# Power_Distribution_Board_B.net
KiCad netlist of a schematic drawn in Altium Designer
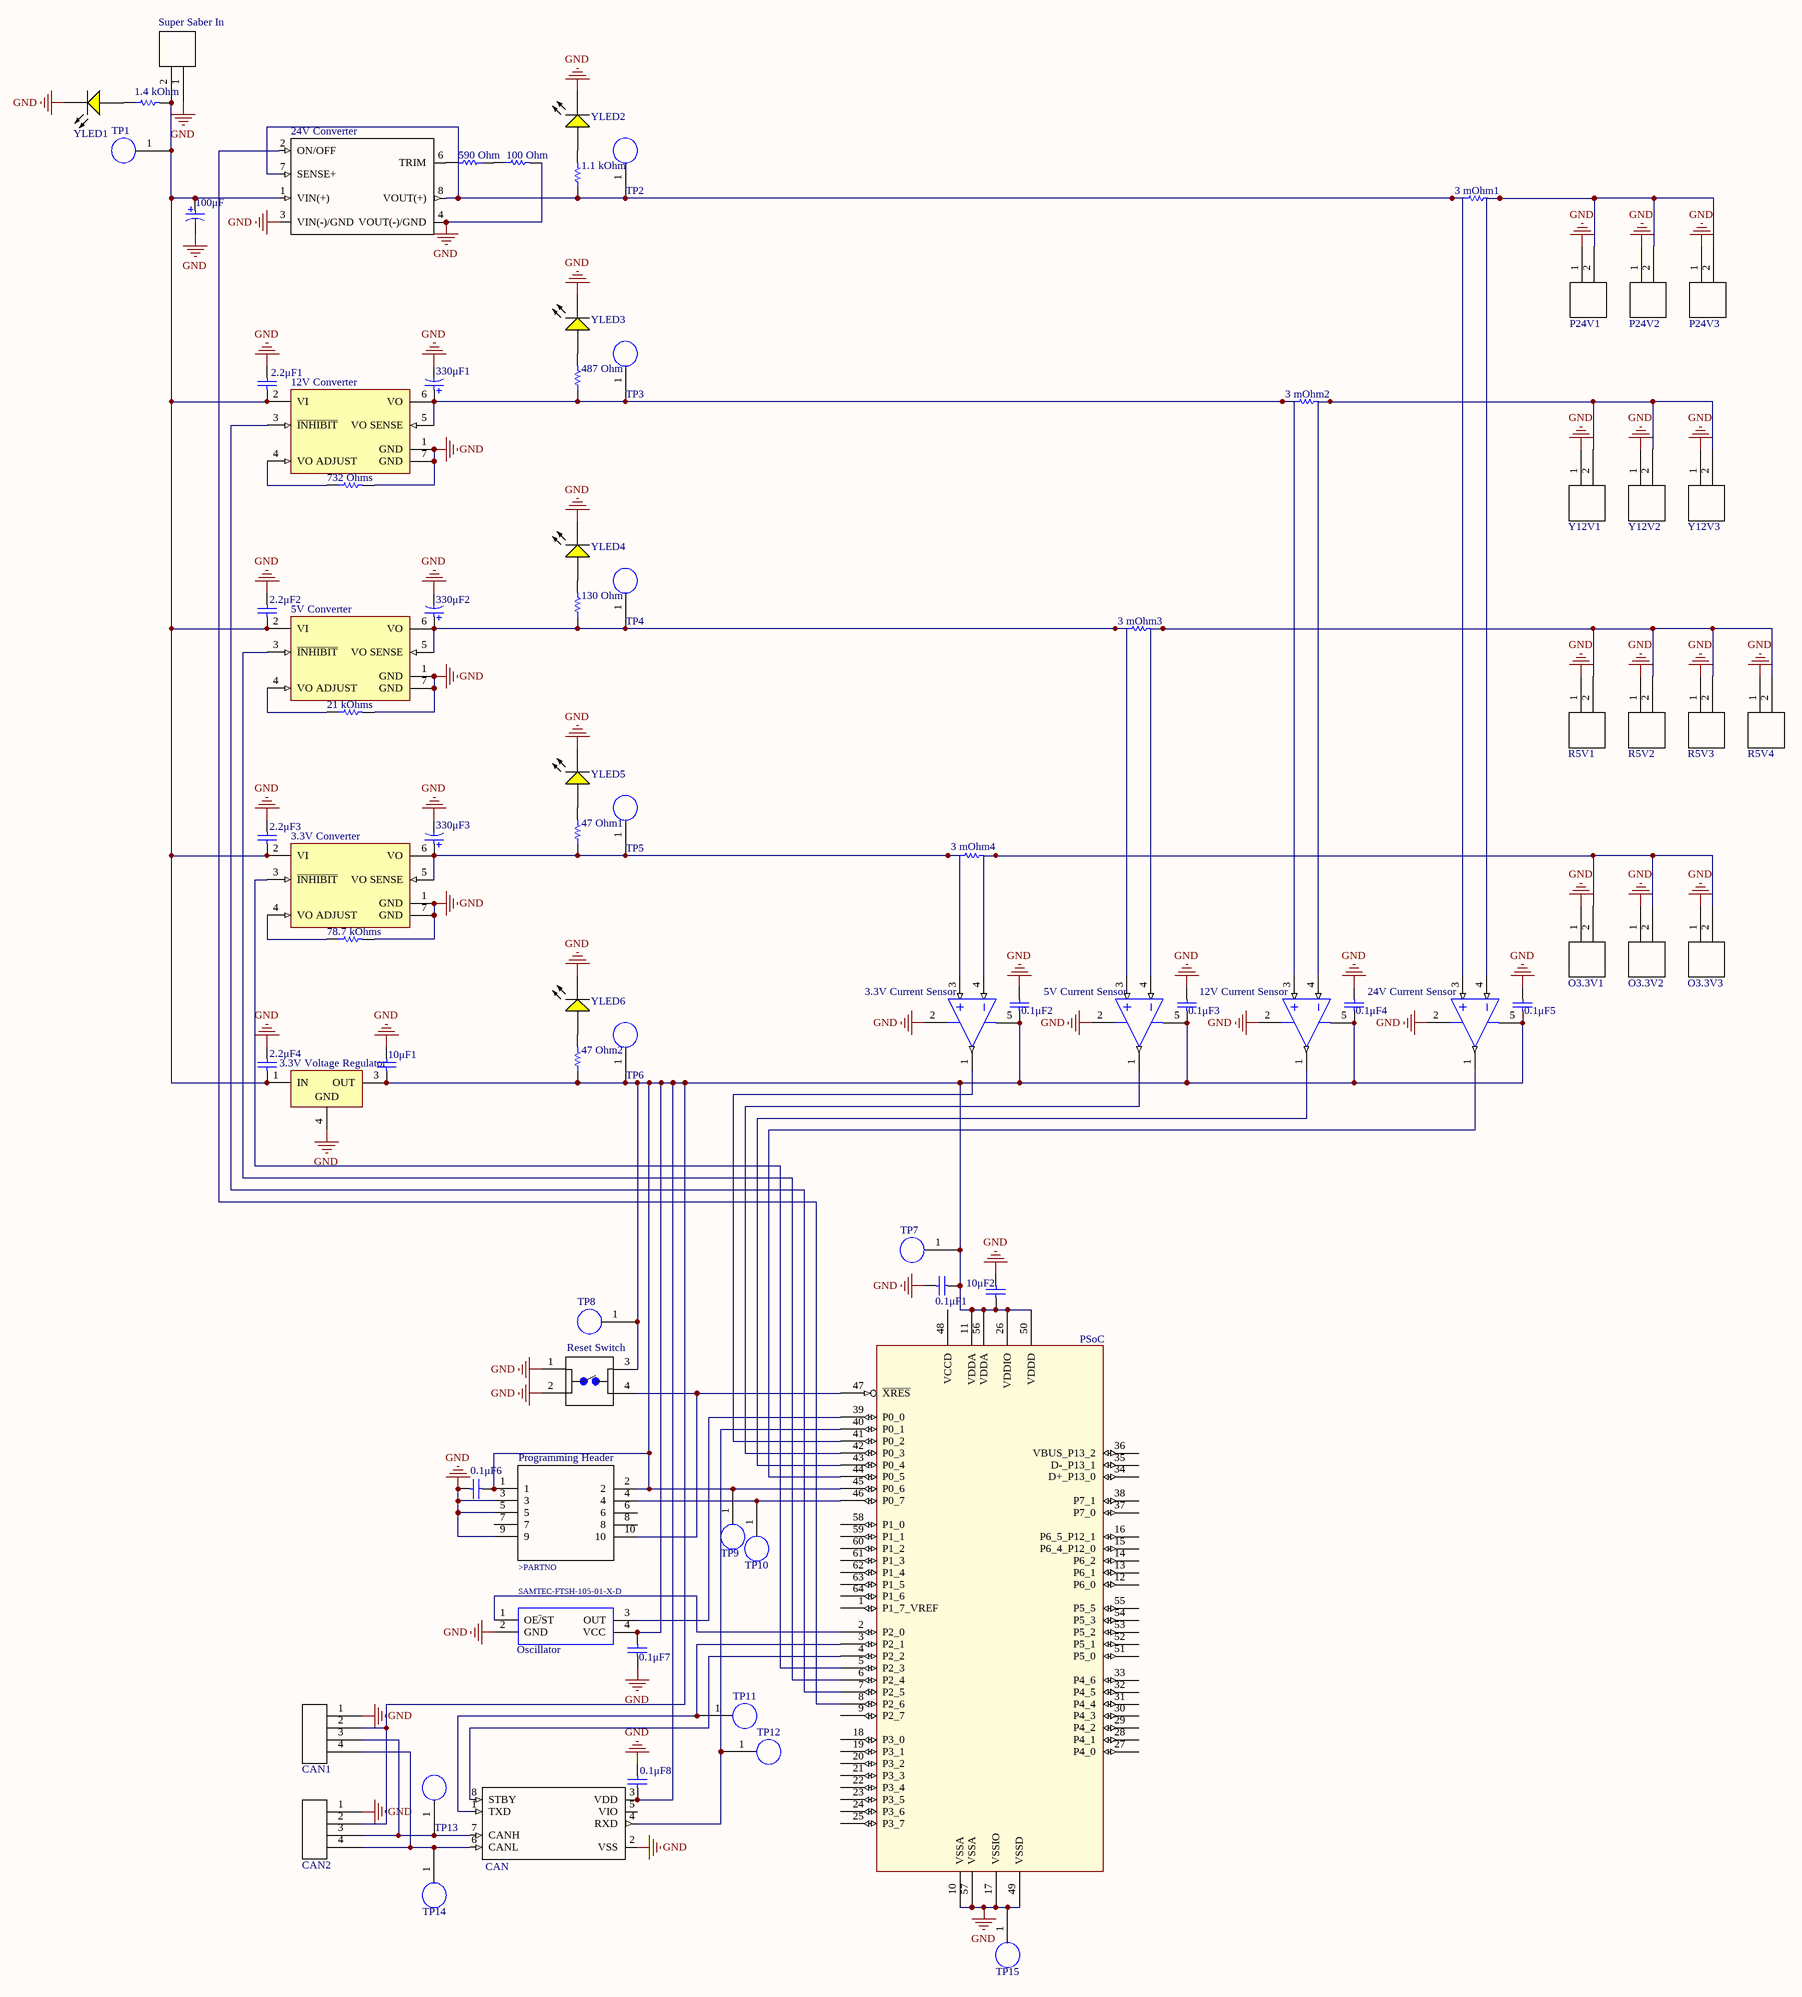
[diagram p0: Power Distribution Board B.SchDoc]

(export (version "E")
  (design (tool "Eeschema 10.0.6"))
  (components
    (comp (ref "0.1μF1")
      (value "C0805C104Z5VACTU")
      (footprint "CAPC2013X145X50LL20T25")
      (fields (field (name "MANUFACTURER") "Kemet"))
      (libsource (lib "Altium Content Vault") (part "CAP"))
    )
    (comp (ref "0.1μF2")
      (value "C0805C104Z5VACTU")
      (footprint "CAPC2013X145X50LL20T25")
      (fields (field (name "MANUFACTURER") "Kemet"))
      (libsource (lib "Altium Content Vault") (part "CAP"))
    )
    (comp (ref "0.1μF3")
      (value "C0805C104Z5VACTU")
      (footprint "CAPC2013X145X50LL20T25")
      (fields (field (name "MANUFACTURER") "Kemet"))
      (libsource (lib "Altium Content Vault") (part "CAP"))
    )
    (comp (ref "0.1μF4")
      (value "C0805C104Z5VACTU")
      (footprint "CAPC2013X145X50LL20T25")
      (fields (field (name "MANUFACTURER") "Kemet"))
      (libsource (lib "Altium Content Vault") (part "CAP"))
    )
    (comp (ref "0.1μF5")
      (value "C0805C104Z5VACTU")
      (footprint "CAPC2013X145X50LL20T25")
      (fields (field (name "MANUFACTURER") "Kemet"))
      (libsource (lib "Altium Content Vault") (part "CAP"))
    )
    (comp (ref "0.1μF6")
      (value "C0805C104Z5VACTU")
      (footprint "CAPC2013X145X50LL20T25")
      (fields (field (name "MANUFACTURER") "Kemet"))
      (libsource (lib "Altium Content Vault") (part "CAP"))
    )
    (comp (ref "0.1μF7")
      (value "C0805C104Z5VACTU")
      (footprint "CAPC2013X145X50LL20T25")
      (fields (field (name "MANUFACTURER") "Kemet"))
      (libsource (lib "Altium Content Vault") (part "CAP"))
    )
    (comp (ref "0.1μF8")
      (value "C0805C104Z5VACTU")
      (footprint "CAPC2013X145X50LL20T25")
      (fields (field (name "MANUFACTURER") "Kemet"))
      (libsource (lib "Altium Content Vault") (part "CAP"))
    )
    (comp (ref "1.1 kOhm")
      (value "ERJ-6GEYJ112V")
      (footprint "RESC2013X70X40ML20T20")
      (fields (field (name "MANUFACTURER") "Panasonic"))
      (libsource (lib "Altium Content Vault") (part "RES"))
    )
    (comp (ref "1.4 kOhm")
      (value "RC0805FR-071K4L")
      (footprint "RESC2013X60X35ML10T20")
      (fields (field (name "MANUFACTURER") "Yageo"))
      (libsource (lib "Altium Content Vault") (part "RES"))
    )
    (comp (ref "2.2μF1")
      (value "C2012X7R1H225K125AC")
      (footprint "CAPC2013X145X20LL20")
      (description "Chip Capacitor, 2.2 uF, +/- 10%, 50 V, -55 to 125 degC, 0805 (2012 Metric), RoHS, Tape and Reel")
      (fields (field (name "MANUFACTURER") "TDK") (field (name "TOLERANCE") "±10%"))
      (libsource (lib "Altium Content Vault") (part "CAP-NP-2"))
    )
    (comp (ref "2.2μF2")
      (value "C2012X7R1H225K125AC")
      (footprint "CAPC2013X145X20LL20")
      (description "Chip Capacitor, 2.2 uF, +/- 10%, 50 V, -55 to 125 degC, 0805 (2012 Metric), RoHS, Tape and Reel")
      (fields (field (name "MANUFACTURER") "TDK") (field (name "TOLERANCE") "±10%"))
      (libsource (lib "Altium Content Vault") (part "CAP-NP-2"))
    )
    (comp (ref "2.2μF3")
      (value "C2012X7R1H225K125AC")
      (footprint "CAPC2013X145X20LL20")
      (description "Chip Capacitor, 2.2 uF, +/- 10%, 50 V, -55 to 125 degC, 0805 (2012 Metric), RoHS, Tape and Reel")
      (fields (field (name "MANUFACTURER") "TDK") (field (name "TOLERANCE") "±10%"))
      (libsource (lib "Altium Content Vault") (part "CAP-NP-2"))
    )
    (comp (ref "2.2μF4")
      (value "C2012X7R1H225K125AC")
      (footprint "CAPC2013X145X20LL20")
      (description "Chip Capacitor, 2.2 uF, +/- 10%, 50 V, -55 to 125 degC, 0805 (2012 Metric), RoHS, Tape and Reel")
      (fields (field (name "MANUFACTURER") "TDK") (field (name "TOLERANCE") "±10%"))
      (libsource (lib "Altium Content Vault") (part "CAP-NP-2"))
    )
    (comp (ref "3 mOhm1")
      (value "OAR5R003JLF")
      (footprint "OAR5R003JLF:OAR5R003JLF")
      (description "Resistor")
      (libsource (lib "Miscellaneous Devices") (part "Res1"))
    )
    (comp (ref "3 mOhm2")
      (value "OAR5R003JLF")
      (footprint "OAR5R003JLF:OAR5R003JLF")
      (description "Resistor")
      (libsource (lib "Miscellaneous Devices") (part "Res1"))
    )
    (comp (ref "3 mOhm3")
      (value "OAR5R003JLF")
      (footprint "OAR5R003JLF:OAR5R003JLF")
      (description "Resistor")
      (libsource (lib "Miscellaneous Devices") (part "Res1"))
    )
    (comp (ref "3 mOhm4")
      (value "OAR5R003JLF")
      (footprint "OAR5R003JLF:OAR5R003JLF")
      (description "Resistor")
      (libsource (lib "Miscellaneous Devices") (part "Res1"))
    )
    (comp (ref "3.3V Converter")
      (value "PTN78020WAH")
      (footprint "TI-EUK7_V")
      (fields (field (name "MANUFACTURER") "Texas Instruments"))
      (libsource (lib "Altium Content Vault") (part "TI-PTN780X0WEUX7_HEUX7"))
    )
    (comp (ref "3.3V Current Sensor")
      (value "INA194AIDBVR")
      (footprint "TI-DBV5_M")
      (fields (field (name "MANUFACTURER") "Texas Instruments"))
      (libsource (lib "Altium Content Vault") (part "TI-INA1XXDBV5"))
    )
    (comp (ref "3.3V Voltage Regulator")
      (value "LP2950CDTX-3.3")
      (footprint "TD03B_M")
      (description "Series of Adjustable Micropower Voltage Regulators, 3-pin TO-252")
      (fields (field (name "MANUFACTURER") "National Semiconductor"))
      (libsource (lib "Altium Content Vault") (part "PM-REG-LM78M05-SOT3"))
    )
    (comp (ref "5V Converter")
      (value "PTN78020WAH")
      (footprint "TI-EUK7_V")
      (fields (field (name "MANUFACTURER") "Texas Instruments"))
      (libsource (lib "Altium Content Vault") (part "TI-PTN780X0WEUX7_HEUX7"))
    )
    (comp (ref "5V Current Sensor")
      (value "INA194AIDBVR")
      (footprint "TI-DBV5_M")
      (fields (field (name "MANUFACTURER") "Texas Instruments"))
      (libsource (lib "Altium Content Vault") (part "TI-INA1XXDBV5"))
    )
    (comp (ref "10μF1")
      (value "TPSR106K006R1000")
      (footprint "CAPC2113X140X50ML20T30")
      (fields (field (name "MANUFACTURER") "AVX Interconnect / Elco"))
      (libsource (lib "Altium Content Vault") (part "CAP"))
    )
    (comp (ref "10μF2")
      (value "TPSR106K006R1000")
      (footprint "CAPC2113X140X50ML20T30")
      (fields (field (name "MANUFACTURER") "AVX Interconnect / Elco"))
      (libsource (lib "Altium Content Vault") (part "CAP"))
    )
    (comp (ref "12V Converter")
      (value "PTN78020WAH")
      (footprint "TI-EUK7_V")
      (fields (field (name "MANUFACTURER") "Texas Instruments"))
      (libsource (lib "Altium Content Vault") (part "TI-PTN780X0WEUX7_HEUX7"))
    )
    (comp (ref "12V Current Sensor")
      (value "INA194AIDBVR")
      (footprint "TI-DBV5_M")
      (fields (field (name "MANUFACTURER") "Texas Instruments"))
      (libsource (lib "Altium Content Vault") (part "TI-INA1XXDBV5"))
    )
    (comp (ref "21 kOhms")
      (value "ERJ-6ENF2102V")
      (footprint "RESC2013X70X40ML20T20")
      (fields (field (name "MANUFACTURER") "Panasonic"))
      (libsource (lib "Altium Content Vault") (part "RES"))
    )
    (comp (ref "24V Converter")
      (value "I6A4W010A033V-001-R")
      (footprint "*TDK-LAMBDA_I6A4W020A033V-001-R")
      (description "Dc-Dc, Pcb Mount, Sixteenth Brick, Input 24vdc, Output 3.3-40v 20a, 250w, Neg Logic")
      (fields (field (name "DIGI-KEY_PART_NUMBER") "285-2670-ND") (field (name "MF") "TDK-Lambda Americas"))
      (libsource (lib "*") (part "I6A4W020A033V-001-R"))
    )
    (comp (ref "24V Current Sensor")
      (value "INA194AIDBVR")
      (footprint "TI-DBV5_M")
      (fields (field (name "MANUFACTURER") "Texas Instruments"))
      (libsource (lib "Altium Content Vault") (part "TI-INA1XXDBV5"))
    )
    (comp (ref "47 Ohm1")
      (value "RR1220Q-470-D")
      (footprint "RESC2013X50X40LL20T20")
      (fields (field (name "MANUFACTURER") "Susumu"))
      (libsource (lib "Altium Content Vault") (part "RES"))
    )
    (comp (ref "47 Ohm2")
      (value "RR1220Q-470-D")
      (footprint "RESC2013X50X40LL20T20")
      (fields (field (name "MANUFACTURER") "Susumu"))
      (libsource (lib "Altium Content Vault") (part "RES"))
    )
    (comp (ref "78.7 kOhms")
      (value "ERJ-6ENF7872V")
      (footprint "RESC2013X70X40LL20T20")
      (fields (field (name "MANUFACTURER") "Panasonic"))
      (libsource (lib "Altium Content Vault") (part "RES"))
    )
    (comp (ref "100 Ohm")
      (value "ERJ-6ENF1000V")
      (footprint "RESC2013X70X40LL20T20")
      (description "Chip Resistor, 100 Ohm, +/- 1%, 0.125 W, -55 to 155 degC, 0805 (2012 Metric), RoHS, Tape and Reel")
      (fields (field (name "MANUFACTURER") "Panasonic"))
      (libsource (lib "Altium Content Vault") (part "RES-2"))
    )
    (comp (ref "100μF")
      (value "EEU-FC1V101")
      (footprint "CAPPRD350W60D800H2000:Model Name")
      (fields (field (name "MANUFACTURER") "Panasonic"))
      (libsource (lib "CAPPRD350W60D800H2000") (part "PNSC-CAP-P-2"))
    )
    (comp (ref "130 Ohm")
      (value "RC0805JR-07130RL")
      (footprint "RESC2013X60X35ML10T20")
      (fields (field (name "MANUFACTURER") "Yageo"))
      (libsource (lib "Altium Content Vault") (part "RES"))
    )
    (comp (ref "330μF1")
      (value "EEU-FC1V331B")
      (footprint "CAPPRD350W60D800H2000:Model Name")
      (fields (field (name "MANUFACTURER") "Panasonic"))
      (libsource (lib "CAPPRD350W60D800H2000") (part "PNSC-CAP-P-2"))
    )
    (comp (ref "330μF2")
      (value "EEU-FC1V331B")
      (footprint "CAPPRD350W60D800H2000:Model Name")
      (fields (field (name "MANUFACTURER") "Panasonic"))
      (libsource (lib "CAPPRD350W60D800H2000") (part "PNSC-CAP-P-2"))
    )
    (comp (ref "330μF3")
      (value "EEU-FC1V331B")
      (footprint "CAPPRD350W60D800H2000:Model Name")
      (fields (field (name "MANUFACTURER") "Panasonic"))
      (libsource (lib "CAPPRD350W60D800H2000") (part "PNSC-CAP-P-2"))
    )
    (comp (ref "487 Ohm")
      (value "RC0805FR-07487RL")
      (footprint "RESC2013X60X35NL10T20")
      (fields (field (name "MANUFACTURER") "Yageo"))
      (libsource (lib "Altium Content Vault") (part "RES"))
    )
    (comp (ref "590 Ohm")
      (value "ERJ-6ENF5900V")
      (footprint "RESC2013X70X40LL20T20")
      (fields (field (name "MANUFACTURER") "Panasonic"))
      (libsource (lib "Altium Content Vault") (part "RES"))
    )
    (comp (ref "732 Ohms")
      (value "ERJ-6ENF7320V")
      (footprint "RESC2013X70X40LL20T20")
      (fields (field (name "MANUFACTURER") "Panasonic"))
      (libsource (lib "Altium Content Vault") (part "RES"))
    )
    (comp (ref "CAN")
      (value "MCP2562-E/SN")
      (footprint "CAN Tranceiver:SOIC127P600X175-8N")
      (description "Microchip MCP2562-E/SN, CAN Transceiver 1MBps 1-channel IEC 61000-4-2, 8-Pin SOIC")
      (fields (field (name "MF") "Microchip"))
      (libsource (lib "*") (part "MCP2562-E/SN"))
    )
    (comp (ref "CAN1")
      (value "Molex Micro")
      (footprint "0430450427")
      (description "Molex micro-fit 3.0 dual row header. P/N 0430450427")
      (libsource (lib "*") (part "Molex micro-fit 4-pin (Single row schematic)"))
    )
    (comp (ref "CAN2")
      (value "Molex Micro")
      (footprint "0430450427")
      (description "Molex micro-fit 3.0 dual row header. P/N 0430450427")
      (libsource (lib "*") (part "Molex micro-fit 4-pin (Single row schematic)"))
    )
    (comp (ref "O3.3V1")
      (value "*")
      (footprint "Connector Footprints:1510482204")
      (libsource (lib "*") (part "Molex 6.5MM  power connector"))
    )
    (comp (ref "O3.3V2")
      (value "*")
      (footprint "Connector Footprints:1510482204")
      (libsource (lib "*") (part "Molex 6.5MM  power connector"))
    )
    (comp (ref "O3.3V3")
      (value "*")
      (footprint "Connector Footprints:1510482204")
      (libsource (lib "*") (part "Molex 6.5MM  power connector"))
    )
    (comp (ref "Oscillator")
      (value "SG-636PCW_50.0000MC3__ROHS")
      (footprint "Model Name")
      (description "Standard Clock Oscillators 50MHz 3.3Volt 100ppm -20C +70C")
      (fields (field (name "MANUFACTURER_PART_NUMBER") "SG-636PCW 50.0000MC3: ROHS"))
      (libsource (lib "*") (part "SG-636"))
    )
    (comp (ref "P24V1")
      (value "*")
      (footprint "Connector Footprints:1510482204")
      (libsource (lib "*") (part "Molex 6.5MM  power connector"))
    )
    (comp (ref "P24V2")
      (value "*")
      (footprint "Connector Footprints:1510482204")
      (libsource (lib "*") (part "Molex 6.5MM  power connector"))
    )
    (comp (ref "P24V3")
      (value "*")
      (footprint "Connector Footprints:1510482204")
      (libsource (lib "*") (part "Molex 6.5MM  power connector"))
    )
    (comp (ref "Programming Header")
      (value "SAMTEC-FTSH-105-01-X-D")
      (footprint "SAMTEC-FTSH-105-01-X-D:SAMTEC-FTSH-105-01-X-D")
      (description "SAMTEC-FTSH-105-01-X-D. Shrouded 10-pin header with .05 in pitch.")
      (libsource (lib "SAMTEC-FTSH-105-01-X-D") (part "SAMTEC-FTSH-105-01-X-D"))
    )
    (comp (ref "PSoC")
      (value "CY8C4248AZI-L485")
      (footprint "PSOC:TQFP50P1200X1200X160-64N")
      (libsource (lib "*") (part "CY8C4248AZI-L485"))
    )
    (comp (ref "R5V1")
      (value "*")
      (footprint "Connector Footprints:1510482204")
      (libsource (lib "*") (part "Molex 6.5MM  power connector"))
    )
    (comp (ref "R5V2")
      (value "*")
      (footprint "Connector Footprints:1510482204")
      (libsource (lib "*") (part "Molex 6.5MM  power connector"))
    )
    (comp (ref "R5V3")
      (value "*")
      (footprint "Connector Footprints:1510482204")
      (libsource (lib "*") (part "Molex 6.5MM  power connector"))
    )
    (comp (ref "R5V4")
      (value "*")
      (footprint "Connector Footprints:1510482204")
      (libsource (lib "*") (part "Molex 6.5MM  power connector"))
    )
    (comp (ref "Reset Switch")
      (value "1825910-7")
      (footprint "Switch 6mm 24V:Switch 6mm 24V (NO)")
      (description "FSM4JAH=6MM TACT SWITCH, HIGH TEMP")
      (fields (field (name "MF") "TE Connectivity") (field (name "DIGI-KEY_PART_NUMBER") "450-1804-ND"))
      (libsource (lib "*") (part "Switch 6mm 24V (NO)"))
    )
    (comp (ref "Super Saber In")
      (value "*")
      (footprint "1510482204")
      (libsource (lib "*") (part "Super Saber"))
    )
    (comp (ref "TP1") (value "*") (footprint "Test Point pad") (libsource (lib "*") (part "Test Point")))
    (comp (ref "TP2") (value "*") (footprint "Test Point pad") (libsource (lib "*") (part "Test Point")))
    (comp (ref "TP3") (value "*") (footprint "Test Point pad") (libsource (lib "*") (part "Test Point")))
    (comp (ref "TP4") (value "*") (footprint "Test Point pad") (libsource (lib "*") (part "Test Point")))
    (comp (ref "TP5") (value "*") (footprint "Test Point pad") (libsource (lib "*") (part "Test Point")))
    (comp (ref "TP6") (value "*") (footprint "Test Point pad") (libsource (lib "*") (part "Test Point")))
    (comp (ref "TP7") (value "*") (footprint "Test Point pad") (libsource (lib "*") (part "Test Point")))
    (comp (ref "TP8")
      (value "*")
      (footprint "Test Point Through-hole")
      (libsource (lib "*") (part "Test Point"))
    )
    (comp (ref "TP9")
      (value "*")
      (footprint "Test Point Through-hole")
      (libsource (lib "*") (part "Test Point"))
    )
    (comp (ref "TP10") (value "*") (footprint "Test Point pad") (libsource (lib "*") (part "Test Point")))
    (comp (ref "TP11") (value "*") (footprint "Test Point pad") (libsource (lib "*") (part "Test Point")))
    (comp (ref "TP12") (value "*") (footprint "Test Point pad") (libsource (lib "*") (part "Test Point")))
    (comp (ref "TP13") (value "*") (footprint "Test Point pad") (libsource (lib "*") (part "Test Point")))
    (comp (ref "TP14") (value "*") (footprint "Test Point pad") (libsource (lib "*") (part "Test Point")))
    (comp (ref "TP15") (value "*") (footprint "Test Point pad") (libsource (lib "*") (part "Test Point")))
    (comp (ref "Y12V1")
      (value "*")
      (footprint "Connector Footprints:1510482204")
      (libsource (lib "*") (part "Molex 6.5MM  power connector"))
    )
    (comp (ref "Y12V2")
      (value "*")
      (footprint "Connector Footprints:1510482204")
      (libsource (lib "*") (part "Molex 6.5MM  power connector"))
    )
    (comp (ref "Y12V3")
      (value "*")
      (footprint "Connector Footprints:1510482204")
      (libsource (lib "*") (part "Molex 6.5MM  power connector"))
    )
    (comp (ref "YLED1")
      (value "LTST-C170KSKT")
      (footprint "LTST-C170KSKT_V")
      (description "LED Yellow, 75 mW, 80 mA, -55 to 85 degC, 2-Pin SMD, RoHS, Tape and Reel")
      (fields (field (name "MANUFACTURER") "Lite-On"))
      (libsource (lib "Altium Content Vault") (part "LED-YELLOW-AK-2"))
    )
    (comp (ref "YLED2")
      (value "LTST-C170KSKT")
      (footprint "LTST-C170KSKT_V")
      (description "LED Yellow, 75 mW, 80 mA, -55 to 85 degC, 2-Pin SMD, RoHS, Tape and Reel")
      (fields (field (name "MANUFACTURER") "Lite-On"))
      (libsource (lib "Altium Content Vault") (part "LED-YELLOW-AK-2"))
    )
    (comp (ref "YLED3")
      (value "LTST-C170KSKT")
      (footprint "LTST-C170KSKT_V")
      (description "LED Yellow, 75 mW, 80 mA, -55 to 85 degC, 2-Pin SMD, RoHS, Tape and Reel")
      (fields (field (name "MANUFACTURER") "Lite-On"))
      (libsource (lib "Altium Content Vault") (part "LED-YELLOW-AK-2"))
    )
    (comp (ref "YLED4")
      (value "LTST-C170KSKT")
      (footprint "LTST-C170KSKT_V")
      (description "LED Yellow, 75 mW, 80 mA, -55 to 85 degC, 2-Pin SMD, RoHS, Tape and Reel")
      (fields (field (name "MANUFACTURER") "Lite-On"))
      (libsource (lib "Altium Content Vault") (part "LED-YELLOW-AK-2"))
    )
    (comp (ref "YLED5")
      (value "LTST-C170KSKT")
      (footprint "LTST-C170KSKT_V")
      (description "LED Yellow, 75 mW, 80 mA, -55 to 85 degC, 2-Pin SMD, RoHS, Tape and Reel")
      (fields (field (name "MANUFACTURER") "Lite-On"))
      (libsource (lib "Altium Content Vault") (part "LED-YELLOW-AK-2"))
    )
    (comp (ref "YLED6")
      (value "LTST-C170KSKT")
      (footprint "LTST-C170KSKT_V")
      (description "LED Yellow, 75 mW, 80 mA, -55 to 85 degC, 2-Pin SMD, RoHS, Tape and Reel")
      (fields (field (name "MANUFACTURER") "Lite-On"))
      (libsource (lib "Altium Content Vault") (part "LED-YELLOW-AK-2"))
    )
  )
  (nets
    (net (code "1") (name "GND") (class "Default")
      (node (ref "0.1μF1") (pin "1") (pinfunction "1_1") (pintype "passive"))
      (node (ref "0.1μF2") (pin "2") (pinfunction "2_2") (pintype "passive"))
      (node (ref "0.1μF3") (pin "2") (pinfunction "2_2") (pintype "passive"))
      (node (ref "0.1μF4") (pin "2") (pinfunction "2_2") (pintype "passive"))
      (node (ref "0.1μF5") (pin "2") (pinfunction "2_2") (pintype "passive"))
      (node (ref "0.1μF6") (pin "1") (pinfunction "1_1") (pintype "passive"))
      (node (ref "0.1μF7") (pin "2") (pinfunction "2_2") (pintype "passive"))
      (node (ref "0.1μF8") (pin "2") (pinfunction "2_2") (pintype "passive"))
      (node (ref "100 Ohm") (pin "2") (pinfunction "2_2") (pintype "passive"))
      (node (ref "100μF") (pin "2") (pinfunction "2_2") (pintype "passive"))
      (node (ref "10μF1") (pin "2") (pinfunction "2_2") (pintype "passive"))
      (node (ref "10μF2") (pin "2") (pinfunction "2_2") (pintype "passive"))
      (node (ref "12V Converter") (pin "1") (pinfunction "GND_1") (pintype "power_in"))
      (node (ref "12V Converter") (pin "7") (pinfunction "GND_7") (pintype "power_in"))
      (node (ref "12V Current Sensor") (pin "2") (pinfunction "GND_2") (pintype "power_in"))
      (node (ref "2.2μF1") (pin "2") (pinfunction "2_2") (pintype "passive"))
      (node (ref "2.2μF2") (pin "2") (pinfunction "2_2") (pintype "passive"))
      (node (ref "2.2μF3") (pin "2") (pinfunction "2_2") (pintype "passive"))
      (node (ref "2.2μF4") (pin "2") (pinfunction "2_2") (pintype "passive"))
      (node (ref "21 kOhms") (pin "2") (pinfunction "2_2") (pintype "passive"))
      (node (ref "24V Converter") (pin "3") (pinfunction "VIN(-)/GND_3") (pintype "power_in"))
      (node (ref "24V Converter") (pin "4") (pinfunction "VOUT(-)/GND_4") (pintype "power_in"))
      (node (ref "24V Current Sensor") (pin "2") (pinfunction "GND_2") (pintype "power_in"))
      (node (ref "3.3V Converter") (pin "1") (pinfunction "GND_1") (pintype "power_in"))
      (node (ref "3.3V Converter") (pin "7") (pinfunction "GND_7") (pintype "power_in"))
      (node (ref "3.3V Current Sensor") (pin "2") (pinfunction "GND_2") (pintype "power_in"))
      (node (ref "3.3V Voltage Regulator") (pin "4") (pinfunction "GND_4") (pintype "power_in"))
      (node (ref "330μF1") (pin "2") (pinfunction "2_2") (pintype "passive"))
      (node (ref "330μF2") (pin "2") (pinfunction "2_2") (pintype "passive"))
      (node (ref "330μF3") (pin "2") (pinfunction "2_2") (pintype "passive"))
      (node (ref "5V Converter") (pin "1") (pinfunction "GND_1") (pintype "power_in"))
      (node (ref "5V Converter") (pin "7") (pinfunction "GND_7") (pintype "power_in"))
      (node (ref "5V Current Sensor") (pin "2") (pinfunction "GND_2") (pintype "power_in"))
      (node (ref "732 Ohms") (pin "2") (pinfunction "2_2") (pintype "passive"))
      (node (ref "78.7 kOhms") (pin "2") (pinfunction "2_2") (pintype "passive"))
      (node (ref "CAN") (pin "2") (pinfunction "VSS_2") (pintype "power_in"))
      (node (ref "CAN1") (pin "1") (pintype "passive"))
      (node (ref "CAN2") (pin "1") (pintype "passive"))
      (node (ref "O3.3V1") (pin "1") (pintype "passive"))
      (node (ref "O3.3V2") (pin "1") (pintype "passive"))
      (node (ref "O3.3V3") (pin "1") (pintype "passive"))
      (node (ref "Oscillator") (pin "2") (pinfunction "GND_2") (pintype "passive"))
      (node (ref "P24V1") (pin "1") (pintype "passive"))
      (node (ref "P24V2") (pin "1") (pintype "passive"))
      (node (ref "P24V3") (pin "1") (pintype "passive"))
      (node (ref "PSoC") (pin "10") (pinfunction "VSSA_10") (pintype "power_in"))
      (node (ref "PSoC") (pin "17") (pinfunction "VSSIO_17") (pintype "power_in"))
      (node (ref "PSoC") (pin "49") (pinfunction "VSSD_49") (pintype "power_in"))
      (node (ref "PSoC") (pin "57") (pinfunction "VSSA_57") (pintype "power_in"))
      (node (ref "Programming Header") (pin "3") (pinfunction "3_3") (pintype "passive"))
      (node (ref "Programming Header") (pin "5") (pinfunction "5_5") (pintype "passive"))
      (node (ref "Programming Header") (pin "9") (pinfunction "9_9") (pintype "passive"))
      (node (ref "R5V1") (pin "1") (pintype "passive"))
      (node (ref "R5V2") (pin "1") (pintype "passive"))
      (node (ref "R5V3") (pin "1") (pintype "passive"))
      (node (ref "R5V4") (pin "1") (pintype "passive"))
      (node (ref "Reset Switch") (pin "1") (pinfunction "1_1") (pintype "passive"))
      (node (ref "Reset Switch") (pin "2") (pinfunction "2_2") (pintype "passive"))
      (node (ref "Super Saber In") (pin "1") (pintype "passive"))
      (node (ref "TP15") (pin "1") (pinfunction "1_1") (pintype "passive"))
      (node (ref "Y12V1") (pin "1") (pintype "passive"))
      (node (ref "Y12V2") (pin "1") (pintype "passive"))
      (node (ref "Y12V3") (pin "1") (pintype "passive"))
      (node (ref "YLED1") (pin "2") (pinfunction "K_2") (pintype "passive"))
      (node (ref "YLED2") (pin "2") (pinfunction "K_2") (pintype "passive"))
      (node (ref "YLED3") (pin "2") (pinfunction "K_2") (pintype "passive"))
      (node (ref "YLED4") (pin "2") (pinfunction "K_2") (pintype "passive"))
      (node (ref "YLED5") (pin "2") (pinfunction "K_2") (pintype "passive"))
      (node (ref "YLED6") (pin "2") (pinfunction "K_2") (pintype "passive"))
    )
    (net (code "2") (name "Net-(3.3V Converter-VO)") (class "Default")
      (node (ref "3 mOhm4") (pin "1") (pinfunction "1_1") (pintype "passive"))
      (node (ref "3.3V Converter") (pin "5") (pinfunction "VO_SENSE_5") (pintype "input"))
      (node (ref "3.3V Converter") (pin "6") (pinfunction "VO_6") (pintype "power_in"))
      (node (ref "3.3V Current Sensor") (pin "3") (pinfunction "VIN+_3") (pintype "input"))
      (node (ref "330μF3") (pin "1") (pinfunction "1_1") (pintype "passive"))
      (node (ref "47 Ohm1") (pin "1") (pinfunction "1_1") (pintype "passive"))
      (node (ref "TP5") (pin "1") (pinfunction "1_1") (pintype "passive"))
    )
    (net (code "3") (name "Net-(3.3V Converter-VO_ADJUST)") (class "Default")
      (node (ref "3.3V Converter") (pin "4") (pinfunction "VO_ADJUST_4") (pintype "input"))
      (node (ref "78.7 kOhms") (pin "1") (pinfunction "1_1") (pintype "passive"))
    )
    (net (code "4") (name "Net-(3.3V Converter-~{INHIBIT})") (class "Default")
      (node (ref "3.3V Converter") (pin "3") (pinfunction "~{INHIBIT}_3") (pintype "input"))
      (node (ref "PSoC") (pin "5") (pinfunction "P2_3_5") (pintype "bidirectional"))
    )
    (net (code "5") (name "Net-(3.3V Current Sensor-OUT)") (class "Default")
      (node (ref "3.3V Current Sensor") (pin "1") (pinfunction "OUT_1") (pintype "output"))
      (node (ref "PSoC") (pin "41") (pinfunction "P0_2_41") (pintype "bidirectional"))
    )
    (net (code "6") (name "Net-(3.3V Current Sensor-VIN-)") (class "Default")
      (node (ref "3 mOhm4") (pin "2") (pinfunction "2_2") (pintype "passive"))
      (node (ref "3.3V Current Sensor") (pin "4") (pinfunction "VIN-_4") (pintype "input"))
      (node (ref "O3.3V1") (pin "2") (pintype "passive"))
      (node (ref "O3.3V2") (pin "2") (pintype "passive"))
      (node (ref "O3.3V3") (pin "2") (pintype "passive"))
    )
    (net (code "7") (name "Net-(5V Converter-VO)") (class "Default")
      (node (ref "130 Ohm") (pin "1") (pinfunction "1_1") (pintype "passive"))
      (node (ref "3 mOhm3") (pin "1") (pinfunction "1_1") (pintype "passive"))
      (node (ref "330μF2") (pin "1") (pinfunction "1_1") (pintype "passive"))
      (node (ref "5V Converter") (pin "5") (pinfunction "VO_SENSE_5") (pintype "input"))
      (node (ref "5V Converter") (pin "6") (pinfunction "VO_6") (pintype "power_in"))
      (node (ref "5V Current Sensor") (pin "3") (pinfunction "VIN+_3") (pintype "input"))
      (node (ref "TP4") (pin "1") (pinfunction "1_1") (pintype "passive"))
    )
    (net (code "8") (name "Net-(5V Converter-VO_ADJUST)") (class "Default")
      (node (ref "21 kOhms") (pin "1") (pinfunction "1_1") (pintype "passive"))
      (node (ref "5V Converter") (pin "4") (pinfunction "VO_ADJUST_4") (pintype "input"))
    )
    (net (code "9") (name "Net-(5V Converter-~{INHIBIT})") (class "Default")
      (node (ref "5V Converter") (pin "3") (pinfunction "~{INHIBIT}_3") (pintype "input"))
      (node (ref "PSoC") (pin "6") (pinfunction "P2_4_6") (pintype "bidirectional"))
    )
    (net (code "10") (name "Net-(5V Current Sensor-OUT)") (class "Default")
      (node (ref "5V Current Sensor") (pin "1") (pinfunction "OUT_1") (pintype "output"))
      (node (ref "PSoC") (pin "42") (pinfunction "P0_3_42") (pintype "bidirectional"))
    )
    (net (code "11") (name "Net-(5V Current Sensor-VIN-)") (class "Default")
      (node (ref "3 mOhm3") (pin "2") (pinfunction "2_2") (pintype "passive"))
      (node (ref "5V Current Sensor") (pin "4") (pinfunction "VIN-_4") (pintype "input"))
      (node (ref "R5V1") (pin "2") (pintype "passive"))
      (node (ref "R5V2") (pin "2") (pintype "passive"))
      (node (ref "R5V3") (pin "2") (pintype "passive"))
      (node (ref "R5V4") (pin "2") (pintype "passive"))
    )
    (net (code "12") (name "Net-(12V Converter-VI)") (class "Default")
      (node (ref "1.4 kOhm") (pin "2") (pinfunction "2_2") (pintype "passive"))
      (node (ref "100μF") (pin "1") (pinfunction "1_1") (pintype "passive"))
      (node (ref "12V Converter") (pin "2") (pinfunction "VI_2") (pintype "power_in"))
      (node (ref "2.2μF1") (pin "1") (pinfunction "1_1") (pintype "passive"))
      (node (ref "2.2μF2") (pin "1") (pinfunction "1_1") (pintype "passive"))
      (node (ref "2.2μF3") (pin "1") (pinfunction "1_1") (pintype "passive"))
      (node (ref "2.2μF4") (pin "1") (pinfunction "1_1") (pintype "passive"))
      (node (ref "24V Converter") (pin "1") (pinfunction "VIN(+)_1") (pintype "input"))
      (node (ref "3.3V Converter") (pin "2") (pinfunction "VI_2") (pintype "power_in"))
      (node (ref "3.3V Voltage Regulator") (pin "1") (pinfunction "IN_1") (pintype "power_in"))
      (node (ref "5V Converter") (pin "2") (pinfunction "VI_2") (pintype "power_in"))
      (node (ref "Super Saber In") (pin "2") (pintype "passive"))
      (node (ref "TP1") (pin "1") (pinfunction "1_1") (pintype "passive"))
    )
    (net (code "13") (name "Net-(12V Converter-VO)") (class "Default")
      (node (ref "12V Converter") (pin "5") (pinfunction "VO_SENSE_5") (pintype "input"))
      (node (ref "12V Converter") (pin "6") (pinfunction "VO_6") (pintype "power_in"))
      (node (ref "12V Current Sensor") (pin "3") (pinfunction "VIN+_3") (pintype "input"))
      (node (ref "3 mOhm2") (pin "1") (pinfunction "1_1") (pintype "passive"))
      (node (ref "330μF1") (pin "1") (pinfunction "1_1") (pintype "passive"))
      (node (ref "487 Ohm") (pin "1") (pinfunction "1_1") (pintype "passive"))
      (node (ref "TP3") (pin "1") (pinfunction "1_1") (pintype "passive"))
    )
    (net (code "14") (name "Net-(12V Converter-VO_ADJUST)") (class "Default")
      (node (ref "12V Converter") (pin "4") (pinfunction "VO_ADJUST_4") (pintype "input"))
      (node (ref "732 Ohms") (pin "1") (pinfunction "1_1") (pintype "passive"))
    )
    (net (code "15") (name "Net-(12V Converter-~{INHIBIT})") (class "Default")
      (node (ref "12V Converter") (pin "3") (pinfunction "~{INHIBIT}_3") (pintype "input"))
      (node (ref "PSoC") (pin "7") (pinfunction "P2_5_7") (pintype "bidirectional"))
    )
    (net (code "16") (name "Net-(12V Current Sensor-OUT)") (class "Default")
      (node (ref "12V Current Sensor") (pin "1") (pinfunction "OUT_1") (pintype "output"))
      (node (ref "PSoC") (pin "43") (pinfunction "P0_4_43") (pintype "bidirectional"))
    )
    (net (code "17") (name "Net-(12V Current Sensor-V+)") (class "Default")
      (node (ref "0.1μF1") (pin "2") (pinfunction "2_2") (pintype "passive"))
      (node (ref "0.1μF2") (pin "1") (pinfunction "1_1") (pintype "passive"))
      (node (ref "0.1μF3") (pin "1") (pinfunction "1_1") (pintype "passive"))
      (node (ref "0.1μF4") (pin "1") (pinfunction "1_1") (pintype "passive"))
      (node (ref "0.1μF5") (pin "1") (pinfunction "1_1") (pintype "passive"))
      (node (ref "0.1μF6") (pin "2") (pinfunction "2_2") (pintype "passive"))
      (node (ref "0.1μF7") (pin "1") (pinfunction "1_1") (pintype "passive"))
      (node (ref "0.1μF8") (pin "1") (pinfunction "1_1") (pintype "passive"))
      (node (ref "10μF1") (pin "1") (pinfunction "1_1") (pintype "passive"))
      (node (ref "10μF2") (pin "1") (pinfunction "1_1") (pintype "passive"))
      (node (ref "12V Current Sensor") (pin "5") (pinfunction "V+_5") (pintype "power_in"))
      (node (ref "24V Current Sensor") (pin "5") (pinfunction "V+_5") (pintype "power_in"))
      (node (ref "3.3V Current Sensor") (pin "5") (pinfunction "V+_5") (pintype "power_in"))
      (node (ref "3.3V Voltage Regulator") (pin "3") (pinfunction "OUT_3") (pintype "power_in"))
      (node (ref "47 Ohm2") (pin "1") (pinfunction "1_1") (pintype "passive"))
      (node (ref "5V Current Sensor") (pin "5") (pinfunction "V+_5") (pintype "power_in"))
      (node (ref "CAN") (pin "3") (pinfunction "VDD_3") (pintype "power_in"))
      (node (ref "CAN1") (pin "2") (pintype "passive"))
      (node (ref "CAN2") (pin "2") (pintype "passive"))
      (node (ref "Oscillator") (pin "4") (pinfunction "VCC_4") (pintype "power_in"))
      (node (ref "PSoC") (pin "11") (pinfunction "VDDA_11") (pintype "power_in"))
      (node (ref "PSoC") (pin "26") (pinfunction "VDDIO_26") (pintype "power_in"))
      (node (ref "PSoC") (pin "45") (pinfunction "P0_6_45") (pintype "bidirectional"))
      (node (ref "PSoC") (pin "50") (pinfunction "VDDD_50") (pintype "power_in"))
      (node (ref "PSoC") (pin "56") (pinfunction "VDDA_56") (pintype "power_in"))
      (node (ref "Programming Header") (pin "1") (pinfunction "1_1") (pintype "passive"))
      (node (ref "Programming Header") (pin "2") (pinfunction "2_2") (pintype "passive"))
      (node (ref "Reset Switch") (pin "3") (pinfunction "3_3") (pintype "passive"))
      (node (ref "TP6") (pin "1") (pinfunction "1_1") (pintype "passive"))
      (node (ref "TP7") (pin "1") (pinfunction "1_1") (pintype "passive"))
      (node (ref "TP8") (pin "1") (pinfunction "1_1") (pintype "passive"))
      (node (ref "TP9") (pin "1") (pinfunction "1_1") (pintype "passive"))
    )
    (net (code "18") (name "Net-(12V Current Sensor-VIN-)") (class "Default")
      (node (ref "12V Current Sensor") (pin "4") (pinfunction "VIN-_4") (pintype "input"))
      (node (ref "3 mOhm2") (pin "2") (pinfunction "2_2") (pintype "passive"))
      (node (ref "Y12V1") (pin "2") (pintype "passive"))
      (node (ref "Y12V2") (pin "2") (pintype "passive"))
      (node (ref "Y12V3") (pin "2") (pintype "passive"))
    )
    (net (code "19") (name "Net-(24V Converter-ON{slash}OFF)") (class "Default")
      (node (ref "24V Converter") (pin "2") (pinfunction "ON/OFF_2") (pintype "input"))
      (node (ref "PSoC") (pin "8") (pinfunction "P2_6_8") (pintype "bidirectional"))
    )
    (net (code "20") (name "Net-(24V Converter-SENSE+)") (class "Default")
      (node (ref "1.1 kOhm") (pin "1") (pinfunction "1_1") (pintype "passive"))
      (node (ref "24V Converter") (pin "7") (pinfunction "SENSE+_7") (pintype "input"))
      (node (ref "24V Converter") (pin "8") (pinfunction "VOUT(+)_8") (pintype "output"))
      (node (ref "24V Current Sensor") (pin "3") (pinfunction "VIN+_3") (pintype "input"))
      (node (ref "3 mOhm1") (pin "1") (pinfunction "1_1") (pintype "passive"))
      (node (ref "TP2") (pin "1") (pinfunction "1_1") (pintype "passive"))
    )
    (net (code "21") (name "Net-(24V Converter-TRIM)") (class "Default")
      (node (ref "24V Converter") (pin "6") (pinfunction "TRIM_6") (pintype "passive"))
      (node (ref "590 Ohm") (pin "2") (pinfunction "2_2") (pintype "passive"))
    )
    (net (code "22") (name "Net-(24V Current Sensor-OUT)") (class "Default")
      (node (ref "24V Current Sensor") (pin "1") (pinfunction "OUT_1") (pintype "output"))
      (node (ref "PSoC") (pin "44") (pinfunction "P0_5_44") (pintype "bidirectional"))
    )
    (net (code "23") (name "Net-(24V Current Sensor-VIN-)") (class "Default")
      (node (ref "24V Current Sensor") (pin "4") (pinfunction "VIN-_4") (pintype "input"))
      (node (ref "3 mOhm1") (pin "2") (pinfunction "2_2") (pintype "passive"))
      (node (ref "P24V1") (pin "2") (pintype "passive"))
      (node (ref "P24V2") (pin "2") (pintype "passive"))
      (node (ref "P24V3") (pin "2") (pintype "passive"))
    )
    (net (code "24") (name "Net-(100 Ohm-Pad1)") (class "Default")
      (node (ref "100 Ohm") (pin "1") (pinfunction "1_1") (pintype "passive"))
      (node (ref "590 Ohm") (pin "1") (pinfunction "1_1") (pintype "passive"))
    )
    (net (code "25") (name "Net-(CAN-CANH)") (class "Default")
      (node (ref "CAN") (pin "7") (pinfunction "CANH_7") (pintype "input"))
      (node (ref "CAN1") (pin "3") (pintype "passive"))
      (node (ref "CAN2") (pin "3") (pintype "passive"))
      (node (ref "TP13") (pin "1") (pinfunction "1_1") (pintype "passive"))
    )
    (net (code "26") (name "Net-(CAN-CANL)") (class "Default")
      (node (ref "CAN") (pin "6") (pinfunction "CANL_6") (pintype "input"))
      (node (ref "CAN1") (pin "4") (pintype "passive"))
      (node (ref "CAN2") (pin "4") (pintype "passive"))
      (node (ref "TP14") (pin "1") (pinfunction "1_1") (pintype "passive"))
    )
    (net (code "27") (name "Net-(CAN-RXD)") (class "Default")
      (node (ref "CAN") (pin "4") (pinfunction "RXD_4") (pintype "output"))
      (node (ref "PSoC") (pin "40") (pinfunction "P0_1_40") (pintype "bidirectional"))
      (node (ref "TP12") (pin "1") (pinfunction "1_1") (pintype "passive"))
    )
    (net (code "28") (name "Net-(CAN-STBY)") (class "Default")
      (node (ref "CAN") (pin "8") (pinfunction "STBY_8") (pintype "input"))
      (node (ref "PSoC") (pin "4") (pinfunction "P2_2_4") (pintype "bidirectional"))
    )
    (net (code "29") (name "Net-(CAN-TXD)") (class "Default")
      (node (ref "CAN") (pin "1") (pinfunction "TXD_1") (pintype "input"))
      (node (ref "PSoC") (pin "3") (pinfunction "P2_1_3") (pintype "bidirectional"))
      (node (ref "TP11") (pin "1") (pinfunction "1_1") (pintype "passive"))
    )
    (net (code "30") (name "Net-(Oscillator-OE~{{slash}}ST)") (class "Default")
      (node (ref "Oscillator") (pin "1") (pinfunction "OE~{/}ST_1") (pintype "passive"))
      (node (ref "PSoC") (pin "2") (pinfunction "P2_0_2") (pintype "bidirectional"))
    )
    (net (code "31") (name "Net-(Oscillator-OUT)") (class "Default")
      (node (ref "Oscillator") (pin "3") (pinfunction "OUT_3") (pintype "passive"))
      (node (ref "PSoC") (pin "39") (pinfunction "P0_0_39") (pintype "bidirectional"))
    )
    (net (code "32") (name "Net-(PSoC-P0_7)") (class "Default")
      (node (ref "PSoC") (pin "46") (pinfunction "P0_7_46") (pintype "bidirectional"))
      (node (ref "Programming Header") (pin "4") (pinfunction "4_4") (pintype "passive"))
      (node (ref "TP10") (pin "1") (pinfunction "1_1") (pintype "passive"))
    )
    (net (code "33") (name "Net-(PSoC-~{XRES})") (class "Default")
      (node (ref "PSoC") (pin "47") (pinfunction "~{XRES}_47") (pintype "input"))
      (node (ref "Programming Header") (pin "10") (pinfunction "10_10") (pintype "passive"))
      (node (ref "Reset Switch") (pin "4") (pinfunction "4_4") (pintype "passive"))
    )
    (net (code "34") (name "Net-(YLED1-A)") (class "Default")
      (node (ref "1.4 kOhm") (pin "1") (pinfunction "1_1") (pintype "passive"))
      (node (ref "YLED1") (pin "1") (pinfunction "A_1") (pintype "passive"))
    )
    (net (code "35") (name "Net-(YLED2-A)") (class "Default")
      (node (ref "1.1 kOhm") (pin "2") (pinfunction "2_2") (pintype "passive"))
      (node (ref "YLED2") (pin "1") (pinfunction "A_1") (pintype "passive"))
    )
    (net (code "36") (name "Net-(YLED3-A)") (class "Default")
      (node (ref "487 Ohm") (pin "2") (pinfunction "2_2") (pintype "passive"))
      (node (ref "YLED3") (pin "1") (pinfunction "A_1") (pintype "passive"))
    )
    (net (code "37") (name "Net-(YLED4-A)") (class "Default")
      (node (ref "130 Ohm") (pin "2") (pinfunction "2_2") (pintype "passive"))
      (node (ref "YLED4") (pin "1") (pinfunction "A_1") (pintype "passive"))
    )
    (net (code "38") (name "Net-(YLED5-A)") (class "Default")
      (node (ref "47 Ohm1") (pin "2") (pinfunction "2_2") (pintype "passive"))
      (node (ref "YLED5") (pin "1") (pinfunction "A_1") (pintype "passive"))
    )
    (net (code "39") (name "Net-(YLED6-A)") (class "Default")
      (node (ref "47 Ohm2") (pin "2") (pinfunction "2_2") (pintype "passive"))
      (node (ref "YLED6") (pin "1") (pinfunction "A_1") (pintype "passive"))
    )
    (net (code "40") (name "unconnected-(CAN-VIO-Pad5)") (class "Default")
      (node (ref "CAN") (pin "5") (pinfunction "VIO_5") (pintype "power_in"))
    )
    (net (code "41") (name "unconnected-(PSoC-D+_P13_0-Pad34)") (class "Default")
      (node (ref "PSoC") (pin "34") (pinfunction "D+_P13_0_34") (pintype "bidirectional"))
    )
    (net (code "42") (name "unconnected-(PSoC-D-_P13_1-Pad35)") (class "Default")
      (node (ref "PSoC") (pin "35") (pinfunction "D-_P13_1_35") (pintype "bidirectional"))
    )
    (net (code "43") (name "unconnected-(PSoC-P1_0-Pad58)") (class "Default")
      (node (ref "PSoC") (pin "58") (pinfunction "P1_0_58") (pintype "bidirectional"))
    )
    (net (code "44") (name "unconnected-(PSoC-P1_1-Pad59)") (class "Default")
      (node (ref "PSoC") (pin "59") (pinfunction "P1_1_59") (pintype "bidirectional"))
    )
    (net (code "45") (name "unconnected-(PSoC-P1_2-Pad60)") (class "Default")
      (node (ref "PSoC") (pin "60") (pinfunction "P1_2_60") (pintype "bidirectional"))
    )
    (net (code "46") (name "unconnected-(PSoC-P1_3-Pad61)") (class "Default")
      (node (ref "PSoC") (pin "61") (pinfunction "P1_3_61") (pintype "bidirectional"))
    )
    (net (code "47") (name "unconnected-(PSoC-P1_4-Pad62)") (class "Default")
      (node (ref "PSoC") (pin "62") (pinfunction "P1_4_62") (pintype "bidirectional"))
    )
    (net (code "48") (name "unconnected-(PSoC-P1_5-Pad63)") (class "Default")
      (node (ref "PSoC") (pin "63") (pinfunction "P1_5_63") (pintype "bidirectional"))
    )
    (net (code "49") (name "unconnected-(PSoC-P1_6-Pad64)") (class "Default")
      (node (ref "PSoC") (pin "64") (pinfunction "P1_6_64") (pintype "bidirectional"))
    )
    (net (code "50") (name "unconnected-(PSoC-P1_7_VREF-Pad1)") (class "Default")
      (node (ref "PSoC") (pin "1") (pinfunction "P1_7_VREF_1") (pintype "bidirectional"))
    )
    (net (code "51") (name "unconnected-(PSoC-P2_7-Pad9)") (class "Default")
      (node (ref "PSoC") (pin "9") (pinfunction "P2_7_9") (pintype "bidirectional"))
    )
    (net (code "52") (name "unconnected-(PSoC-P3_0-Pad18)") (class "Default")
      (node (ref "PSoC") (pin "18") (pinfunction "P3_0_18") (pintype "bidirectional"))
    )
    (net (code "53") (name "unconnected-(PSoC-P3_1-Pad19)") (class "Default")
      (node (ref "PSoC") (pin "19") (pinfunction "P3_1_19") (pintype "bidirectional"))
    )
    (net (code "54") (name "unconnected-(PSoC-P3_2-Pad20)") (class "Default")
      (node (ref "PSoC") (pin "20") (pinfunction "P3_2_20") (pintype "bidirectional"))
    )
    (net (code "55") (name "unconnected-(PSoC-P3_3-Pad21)") (class "Default")
      (node (ref "PSoC") (pin "21") (pinfunction "P3_3_21") (pintype "bidirectional"))
    )
    (net (code "56") (name "unconnected-(PSoC-P3_4-Pad22)") (class "Default")
      (node (ref "PSoC") (pin "22") (pinfunction "P3_4_22") (pintype "bidirectional"))
    )
    (net (code "57") (name "unconnected-(PSoC-P3_5-Pad23)") (class "Default")
      (node (ref "PSoC") (pin "23") (pinfunction "P3_5_23") (pintype "bidirectional"))
    )
    (net (code "58") (name "unconnected-(PSoC-P3_6-Pad24)") (class "Default")
      (node (ref "PSoC") (pin "24") (pinfunction "P3_6_24") (pintype "bidirectional"))
    )
    (net (code "59") (name "unconnected-(PSoC-P3_7-Pad25)") (class "Default")
      (node (ref "PSoC") (pin "25") (pinfunction "P3_7_25") (pintype "bidirectional"))
    )
    (net (code "60") (name "unconnected-(PSoC-P4_0-Pad27)") (class "Default")
      (node (ref "PSoC") (pin "27") (pinfunction "P4_0_27") (pintype "bidirectional"))
    )
    (net (code "61") (name "unconnected-(PSoC-P4_1-Pad28)") (class "Default")
      (node (ref "PSoC") (pin "28") (pinfunction "P4_1_28") (pintype "bidirectional"))
    )
    (net (code "62") (name "unconnected-(PSoC-P4_2-Pad29)") (class "Default")
      (node (ref "PSoC") (pin "29") (pinfunction "P4_2_29") (pintype "bidirectional"))
    )
    (net (code "63") (name "unconnected-(PSoC-P4_3-Pad30)") (class "Default")
      (node (ref "PSoC") (pin "30") (pinfunction "P4_3_30") (pintype "bidirectional"))
    )
    (net (code "64") (name "unconnected-(PSoC-P4_4-Pad31)") (class "Default")
      (node (ref "PSoC") (pin "31") (pinfunction "P4_4_31") (pintype "bidirectional"))
    )
    (net (code "65") (name "unconnected-(PSoC-P4_5-Pad32)") (class "Default")
      (node (ref "PSoC") (pin "32") (pinfunction "P4_5_32") (pintype "bidirectional"))
    )
    (net (code "66") (name "unconnected-(PSoC-P4_6-Pad33)") (class "Default")
      (node (ref "PSoC") (pin "33") (pinfunction "P4_6_33") (pintype "bidirectional"))
    )
    (net (code "67") (name "unconnected-(PSoC-P5_0-Pad51)") (class "Default")
      (node (ref "PSoC") (pin "51") (pinfunction "P5_0_51") (pintype "bidirectional"))
    )
    (net (code "68") (name "unconnected-(PSoC-P5_1-Pad52)") (class "Default")
      (node (ref "PSoC") (pin "52") (pinfunction "P5_1_52") (pintype "bidirectional"))
    )
    (net (code "69") (name "unconnected-(PSoC-P5_2-Pad53)") (class "Default")
      (node (ref "PSoC") (pin "53") (pinfunction "P5_2_53") (pintype "bidirectional"))
    )
    (net (code "70") (name "unconnected-(PSoC-P5_3-Pad54)") (class "Default")
      (node (ref "PSoC") (pin "54") (pinfunction "P5_3_54") (pintype "bidirectional"))
    )
    (net (code "71") (name "unconnected-(PSoC-P5_5-Pad55)") (class "Default")
      (node (ref "PSoC") (pin "55") (pinfunction "P5_5_55") (pintype "bidirectional"))
    )
    (net (code "72") (name "unconnected-(PSoC-P6_0-Pad12)") (class "Default")
      (node (ref "PSoC") (pin "12") (pinfunction "P6_0_12") (pintype "bidirectional"))
    )
    (net (code "73") (name "unconnected-(PSoC-P6_1-Pad13)") (class "Default")
      (node (ref "PSoC") (pin "13") (pinfunction "P6_1_13") (pintype "bidirectional"))
    )
    (net (code "74") (name "unconnected-(PSoC-P6_2-Pad14)") (class "Default")
      (node (ref "PSoC") (pin "14") (pinfunction "P6_2_14") (pintype "bidirectional"))
    )
    (net (code "75") (name "unconnected-(PSoC-P6_4_P12_0-Pad15)") (class "Default")
      (node (ref "PSoC") (pin "15") (pinfunction "P6_4_P12_0_15") (pintype "bidirectional"))
    )
    (net (code "76") (name "unconnected-(PSoC-P6_5_P12_1-Pad16)") (class "Default")
      (node (ref "PSoC") (pin "16") (pinfunction "P6_5_P12_1_16") (pintype "bidirectional"))
    )
    (net (code "77") (name "unconnected-(PSoC-P7_0-Pad37)") (class "Default")
      (node (ref "PSoC") (pin "37") (pinfunction "P7_0_37") (pintype "bidirectional"))
    )
    (net (code "78") (name "unconnected-(PSoC-P7_1-Pad38)") (class "Default")
      (node (ref "PSoC") (pin "38") (pinfunction "P7_1_38") (pintype "bidirectional"))
    )
    (net (code "79") (name "unconnected-(PSoC-VBUS_P13_2-Pad36)") (class "Default")
      (node (ref "PSoC") (pin "36") (pinfunction "VBUS_P13_2_36") (pintype "bidirectional"))
    )
    (net (code "80") (name "unconnected-(PSoC-VCCD-Pad48)") (class "Default")
      (node (ref "PSoC") (pin "48") (pinfunction "VCCD_48") (pintype "power_in"))
    )
    (net (code "81") (name "unconnected-(Programming Header-Pad6)") (class "Default")
      (node (ref "Programming Header") (pin "6") (pinfunction "6_6") (pintype "passive"))
    )
    (net (code "82") (name "unconnected-(Programming Header-Pad7)") (class "Default")
      (node (ref "Programming Header") (pin "7") (pinfunction "7_7") (pintype "passive"))
    )
    (net (code "83") (name "unconnected-(Programming Header-Pad8)") (class "Default")
      (node (ref "Programming Header") (pin "8") (pinfunction "8_8") (pintype "passive"))
    )
  )
)
